# Inter_IIT.net
KiCad netlist of a schematic drawn in EAGLE
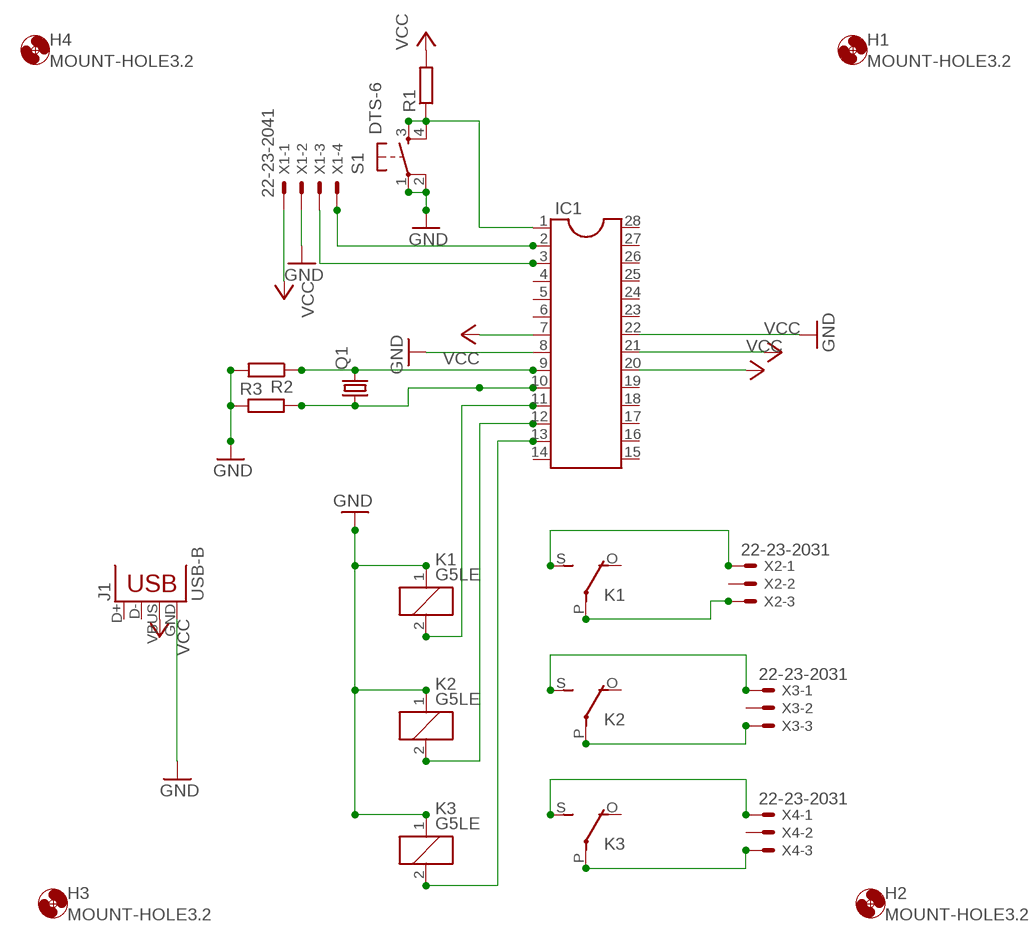
[diagram p0: schematic, sheet 1]

(export (version "E")
  (design (tool "Eeschema 10.0.6"))
  (components
    (comp (ref "H1")
      (value "MOUNT-HOLE3.2")
      (footprint "eagle-import:3,2")
      (libsource (lib "eagle-import") (part "MOUNT-HOLE3.2"))
    )
    (comp (ref "H2")
      (value "MOUNT-HOLE3.2")
      (footprint "eagle-import:3,2")
      (libsource (lib "eagle-import") (part "MOUNT-HOLE3.2"))
    )
    (comp (ref "H3")
      (value "MOUNT-HOLE3.2")
      (footprint "eagle-import:3,2")
      (libsource (lib "eagle-import") (part "MOUNT-HOLE3.2"))
    )
    (comp (ref "H4")
      (value "MOUNT-HOLE3.2")
      (footprint "eagle-import:3,2")
      (libsource (lib "eagle-import") (part "MOUNT-HOLE3.2"))
    )
    (comp (ref "IC1")
      (value "DIL28-3")
      (footprint "eagle-import:DIL28-3")
      (libsource (lib "eagle-import") (part "DIL28-3"))
    )
    (comp (ref "J1")
      (value "USB-B")
      (footprint "eagle-import:USB-B-PTH")
      (libsource (lib "eagle-import") (part "USBPTH"))
    )
    (comp (ref "K1")
      (value "G5LE")
      (footprint "eagle-import:G5LE")
      (libsource (lib "eagle-import") (part "G5LE"))
    )
    (comp (ref "K2")
      (value "G5LE")
      (footprint "eagle-import:G5LE")
      (libsource (lib "eagle-import") (part "G5LE"))
    )
    (comp (ref "K3")
      (value "G5LE")
      (footprint "eagle-import:G5LE")
      (libsource (lib "eagle-import") (part "G5LE"))
    )
    (comp (ref "Q1")
      (value "CRYSTALHC49S")
      (footprint "eagle-import:HC49_S")
      (libsource (lib "eagle-import") (part "CRYSTALHC49S"))
    )
    (comp (ref "R1")
      (value "RESISTOR7.5MM")
      (footprint "eagle-import:RESISTOR7.5MM")
      (libsource (lib "eagle-import") (part "RESISTOR7.5MM"))
    )
    (comp (ref "R2")
      (value "RESISTOR7.5MM")
      (footprint "eagle-import:RESISTOR7.5MM")
      (libsource (lib "eagle-import") (part "RESISTOR7.5MM"))
    )
    (comp (ref "R3")
      (value "RESISTOR7.5MM")
      (footprint "eagle-import:RESISTOR7.5MM")
      (libsource (lib "eagle-import") (part "RESISTOR7.5MM"))
    )
    (comp (ref "S1")
      (value "DTS-6")
      (footprint "eagle-import:DTS-6")
      (libsource (lib "eagle-import") (part "DTS-6"))
    )
    (comp (ref "X1")
      (value "22-23-2041")
      (footprint "eagle-import:22-23-2041")
      (fields (field (name "MF") "MOLEX"))
      (libsource (lib "eagle-import") (part "22-23-2041"))
    )
    (comp (ref "X2")
      (value "22-23-2031")
      (footprint "eagle-import:22-23-2031")
      (fields (field (name "MF") "MOLEX"))
      (libsource (lib "eagle-import") (part "22-23-2031"))
    )
    (comp (ref "X3")
      (value "22-23-2031")
      (footprint "eagle-import:22-23-2031")
      (fields (field (name "MF") "MOLEX"))
      (libsource (lib "eagle-import") (part "22-23-2031"))
    )
    (comp (ref "X4")
      (value "22-23-2031")
      (footprint "eagle-import:22-23-2031")
      (fields (field (name "MF") "MOLEX"))
      (libsource (lib "eagle-import") (part "22-23-2031"))
    )
  )
  (nets
    (net (code "1") (name "GND") (class "Default")
      (node (ref "IC1") (pin "22") (pinfunction "22_22") (pintype "passive"))
      (node (ref "IC1") (pin "8") (pinfunction "8_8") (pintype "passive"))
      (node (ref "J1") (pin "GND") (pinfunction "GND_GND") (pintype "bidirectional"))
      (node (ref "K1") (pin "1") (pinfunction "1_1") (pintype "passive"))
      (node (ref "K2") (pin "1") (pinfunction "1_1") (pintype "passive"))
      (node (ref "K3") (pin "1") (pinfunction "1_1") (pintype "passive"))
      (node (ref "R2") (pin "2") (pinfunction "2_2") (pintype "passive"))
      (node (ref "R3") (pin "1") (pinfunction "1_1") (pintype "passive"))
      (node (ref "S1") (pin "1") (pinfunction "1_1") (pintype "passive"))
      (node (ref "S1") (pin "2") (pinfunction "2_2") (pintype "passive"))
      (node (ref "X1") (pin "2") (pinfunction "S_2") (pintype "passive"))
    )
    (net (code "2") (name "Net-(IC1-Pad1)") (class "Default")
      (node (ref "IC1") (pin "1") (pinfunction "1_1") (pintype "passive"))
      (node (ref "R1") (pin "1") (pinfunction "1_1") (pintype "passive"))
      (node (ref "S1") (pin "3") (pinfunction "3_3") (pintype "passive"))
      (node (ref "S1") (pin "4") (pinfunction "4_4") (pintype "passive"))
    )
    (net (code "3") (name "Net-(IC1-Pad9)") (class "Default")
      (node (ref "IC1") (pin "9") (pinfunction "9_9") (pintype "passive"))
      (node (ref "Q1") (pin "2") (pinfunction "2_2") (pintype "passive"))
      (node (ref "R2") (pin "1") (pinfunction "1_1") (pintype "passive"))
    )
    (net (code "4") (name "Net-(IC1-Pad10)") (class "Default")
      (node (ref "IC1") (pin "10") (pinfunction "10_10") (pintype "passive"))
      (node (ref "Q1") (pin "1") (pinfunction "1_1") (pintype "passive"))
      (node (ref "R3") (pin "2") (pinfunction "2_2") (pintype "passive"))
    )
    (net (code "5") (name "Net-(IC1-Pad11)") (class "Default")
      (node (ref "IC1") (pin "11") (pinfunction "11_11") (pintype "passive"))
      (node (ref "K1") (pin "2") (pinfunction "2_2") (pintype "passive"))
    )
    (net (code "6") (name "Net-(IC1-Pad12)") (class "Default")
      (node (ref "IC1") (pin "12") (pinfunction "12_12") (pintype "passive"))
      (node (ref "K2") (pin "2") (pinfunction "2_2") (pintype "passive"))
    )
    (net (code "7") (name "Net-(IC1-Pad13)") (class "Default")
      (node (ref "IC1") (pin "13") (pinfunction "13_13") (pintype "passive"))
      (node (ref "K3") (pin "2") (pinfunction "2_2") (pintype "passive"))
    )
    (net (code "8") (name "Net-(X1C-S)") (class "Default")
      (node (ref "IC1") (pin "3") (pinfunction "3_3") (pintype "passive"))
      (node (ref "X1") (pin "3") (pinfunction "S_3") (pintype "passive"))
    )
    (net (code "9") (name "Net-(X1D-S)") (class "Default")
      (node (ref "IC1") (pin "2") (pinfunction "2_2") (pintype "passive"))
      (node (ref "X1") (pin "4") (pinfunction "S_4") (pintype "passive"))
    )
    (net (code "10") (name "Net-(X2A-S)") (class "Default")
      (node (ref "K1") (pin "S") (pinfunction "S_S") (pintype "passive"))
      (node (ref "X2") (pin "1") (pinfunction "S_1") (pintype "passive"))
    )
    (net (code "11") (name "Net-(X2C-S)") (class "Default")
      (node (ref "K1") (pin "P") (pinfunction "P_P") (pintype "passive"))
      (node (ref "X2") (pin "3") (pinfunction "S_3") (pintype "passive"))
    )
    (net (code "12") (name "Net-(X3A-S)") (class "Default")
      (node (ref "K2") (pin "S") (pinfunction "S_S") (pintype "passive"))
      (node (ref "X3") (pin "1") (pinfunction "S_1") (pintype "passive"))
    )
    (net (code "13") (name "Net-(X3C-S)") (class "Default")
      (node (ref "K2") (pin "P") (pinfunction "P_P") (pintype "passive"))
      (node (ref "X3") (pin "3") (pinfunction "S_3") (pintype "passive"))
    )
    (net (code "14") (name "Net-(X4A-S)") (class "Default")
      (node (ref "K3") (pin "S") (pinfunction "S_S") (pintype "passive"))
      (node (ref "X4") (pin "1") (pinfunction "S_1") (pintype "passive"))
    )
    (net (code "15") (name "Net-(X4C-S)") (class "Default")
      (node (ref "K3") (pin "P") (pinfunction "P_P") (pintype "passive"))
      (node (ref "X4") (pin "3") (pinfunction "S_3") (pintype "passive"))
    )
    (net (code "16") (name "VCC") (class "Default")
      (node (ref "IC1") (pin "20") (pinfunction "20_20") (pintype "passive"))
      (node (ref "IC1") (pin "21") (pinfunction "21_21") (pintype "passive"))
      (node (ref "IC1") (pin "7") (pinfunction "7_7") (pintype "passive"))
      (node (ref "J1") (pin "VBUS") (pinfunction "VBUS_VBUS") (pintype "bidirectional"))
      (node (ref "R1") (pin "2") (pinfunction "2_2") (pintype "passive"))
      (node (ref "X1") (pin "1") (pinfunction "S_1") (pintype "passive"))
    )
    (net (code "17") (name "unconnected-(IC1-Pad4)") (class "Default")
      (node (ref "IC1") (pin "4") (pinfunction "4_4") (pintype "passive"))
    )
    (net (code "18") (name "unconnected-(IC1-Pad5)") (class "Default")
      (node (ref "IC1") (pin "5") (pinfunction "5_5") (pintype "passive"))
    )
    (net (code "19") (name "unconnected-(IC1-Pad6)") (class "Default")
      (node (ref "IC1") (pin "6") (pinfunction "6_6") (pintype "passive"))
    )
    (net (code "20") (name "unconnected-(IC1-Pad14)") (class "Default")
      (node (ref "IC1") (pin "14") (pinfunction "14_14") (pintype "passive"))
    )
    (net (code "21") (name "unconnected-(IC1-Pad15)") (class "Default")
      (node (ref "IC1") (pin "15") (pinfunction "15_15") (pintype "passive"))
    )
    (net (code "22") (name "unconnected-(IC1-Pad16)") (class "Default")
      (node (ref "IC1") (pin "16") (pinfunction "16_16") (pintype "passive"))
    )
    (net (code "23") (name "unconnected-(IC1-Pad17)") (class "Default")
      (node (ref "IC1") (pin "17") (pinfunction "17_17") (pintype "passive"))
    )
    (net (code "24") (name "unconnected-(IC1-Pad18)") (class "Default")
      (node (ref "IC1") (pin "18") (pinfunction "18_18") (pintype "passive"))
    )
    (net (code "25") (name "unconnected-(IC1-Pad19)") (class "Default")
      (node (ref "IC1") (pin "19") (pinfunction "19_19") (pintype "passive"))
    )
    (net (code "26") (name "unconnected-(IC1-Pad23)") (class "Default")
      (node (ref "IC1") (pin "23") (pinfunction "23_23") (pintype "passive"))
    )
    (net (code "27") (name "unconnected-(IC1-Pad24)") (class "Default")
      (node (ref "IC1") (pin "24") (pinfunction "24_24") (pintype "passive"))
    )
    (net (code "28") (name "unconnected-(IC1-Pad25)") (class "Default")
      (node (ref "IC1") (pin "25") (pinfunction "25_25") (pintype "passive"))
    )
    (net (code "29") (name "unconnected-(IC1-Pad26)") (class "Default")
      (node (ref "IC1") (pin "26") (pinfunction "26_26") (pintype "passive"))
    )
    (net (code "30") (name "unconnected-(IC1-Pad27)") (class "Default")
      (node (ref "IC1") (pin "27") (pinfunction "27_27") (pintype "passive"))
    )
    (net (code "31") (name "unconnected-(IC1-Pad28)") (class "Default")
      (node (ref "IC1") (pin "28") (pinfunction "28_28") (pintype "passive"))
    )
    (net (code "32") (name "unconnected-(J1-PadD+)") (class "Default")
      (node (ref "J1") (pin "D+") (pinfunction "D+_D+") (pintype "bidirectional"))
    )
    (net (code "33") (name "unconnected-(J1-PadD-)") (class "Default")
      (node (ref "J1") (pin "D-") (pinfunction "D-_D-") (pintype "bidirectional"))
    )
    (net (code "34") (name "unconnected-(K1-PadO)") (class "Default")
      (node (ref "K1") (pin "O") (pinfunction "O_O") (pintype "passive"))
    )
    (net (code "35") (name "unconnected-(K2-PadO)") (class "Default")
      (node (ref "K2") (pin "O") (pinfunction "O_O") (pintype "passive"))
    )
    (net (code "36") (name "unconnected-(K3-PadO)") (class "Default")
      (node (ref "K3") (pin "O") (pinfunction "O_O") (pintype "passive"))
    )
    (net (code "37") (name "unconnected-(X2B-S-Pad2)") (class "Default")
      (node (ref "X2") (pin "2") (pinfunction "S_2") (pintype "passive"))
    )
    (net (code "38") (name "unconnected-(X3B-S-Pad2)") (class "Default")
      (node (ref "X3") (pin "2") (pinfunction "S_2") (pintype "passive"))
    )
    (net (code "39") (name "unconnected-(X4B-S-Pad2)") (class "Default")
      (node (ref "X4") (pin "2") (pinfunction "S_2") (pintype "passive"))
    )
  )
)
